# parport.net
KiCad netlist of a schematic drawn in EAGLE
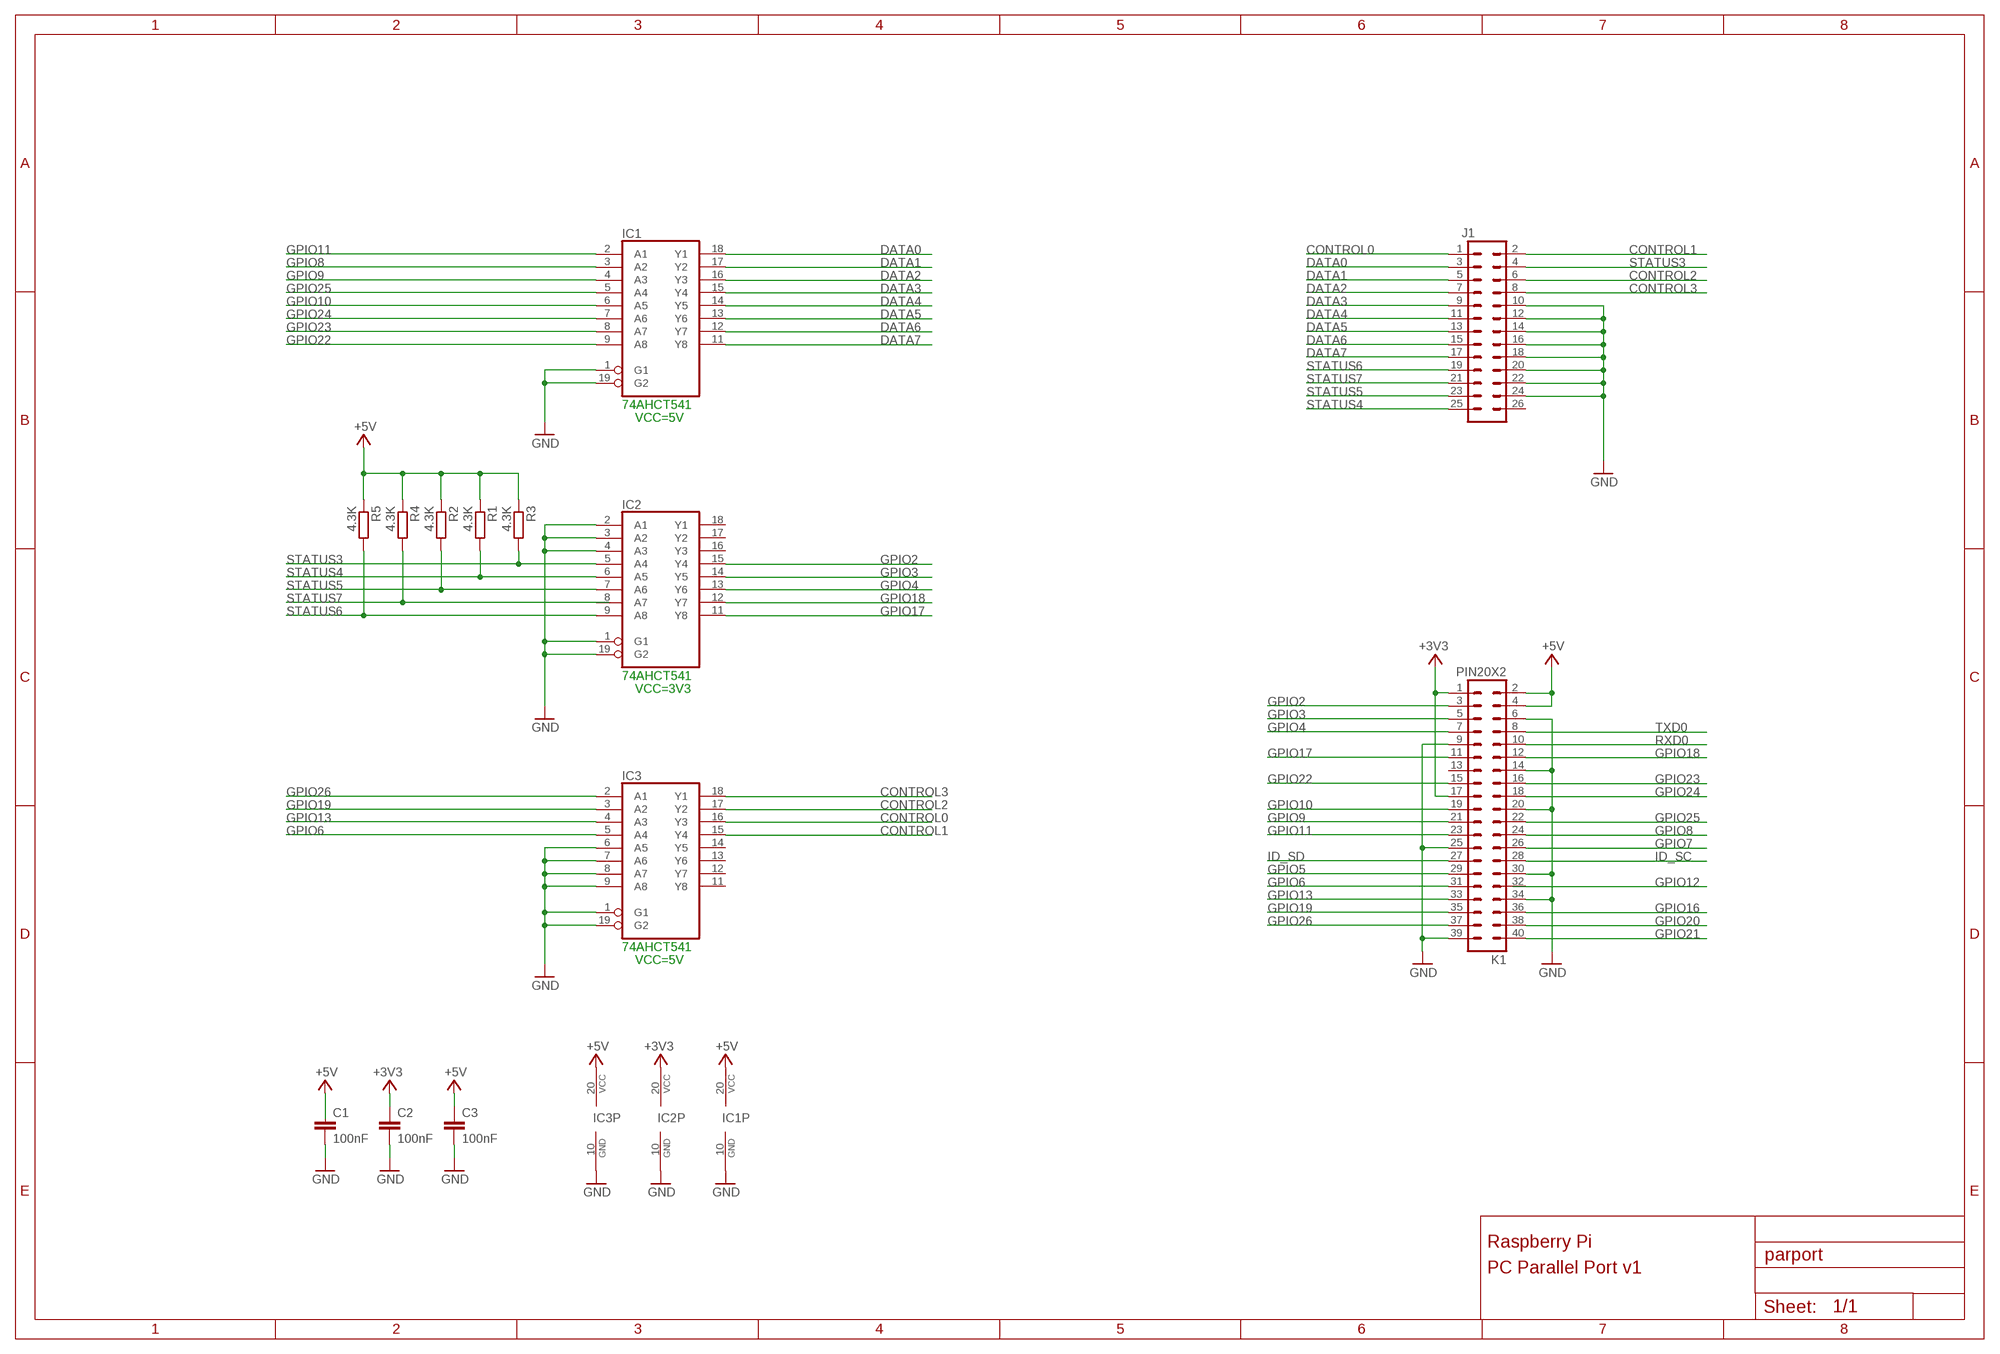
[diagram p0: schematic, sheet 1]

(export (version "E")
  (design (tool "Eeschema 10.0.6"))
  (components
    (comp (ref "C1")
      (value "100nF")
      (footprint "eagle-import:C0805")
      (libsource (lib "eagle-import") (part "C-EUC0805"))
    )
    (comp (ref "C2")
      (value "100nF")
      (footprint "eagle-import:C0805")
      (libsource (lib "eagle-import") (part "C-EUC0805"))
    )
    (comp (ref "C3")
      (value "100nF")
      (footprint "eagle-import:C0805")
      (libsource (lib "eagle-import") (part "C-EUC0805"))
    )
    (comp (ref "IC1")
      (value "74LS541DW")
      (footprint "eagle-import:SO20W")
      (libsource (lib "eagle-import") (part "74541DWLS"))
    )
    (comp (ref "IC2")
      (value "74LS541DW")
      (footprint "eagle-import:SO20W")
      (libsource (lib "eagle-import") (part "74541DWLS"))
    )
    (comp (ref "IC3")
      (value "74LS541DW")
      (footprint "eagle-import:SO20W")
      (libsource (lib "eagle-import") (part "74541DWLS"))
    )
    (comp (ref "J1")
      (value "M13X22X13")
      (footprint "eagle-import:2X13")
      (libsource (lib "eagle-import") (part "M13X22X13"))
    )
    (comp (ref "K1")
      (value "PIN20X2")
      (footprint "eagle-import:PIN_20X2")
      (libsource (lib "eagle-import") (part "PIN20X2"))
    )
    (comp (ref "R1")
      (value "4.3K")
      (footprint "eagle-import:R0805")
      (libsource (lib "eagle-import") (part "R-EU_R0805"))
    )
    (comp (ref "R2")
      (value "4.3K")
      (footprint "eagle-import:R0805")
      (libsource (lib "eagle-import") (part "R-EU_R0805"))
    )
    (comp (ref "R3")
      (value "4.3K")
      (footprint "eagle-import:R0805")
      (libsource (lib "eagle-import") (part "R-EU_R0805"))
    )
    (comp (ref "R4")
      (value "4.3K")
      (footprint "eagle-import:R0805")
      (libsource (lib "eagle-import") (part "R-EU_R0805"))
    )
    (comp (ref "R5")
      (value "4.3K")
      (footprint "eagle-import:R0805")
      (libsource (lib "eagle-import") (part "R-EU_R0805"))
    )
  )
  (nets
    (net (code "1") (name "+3V3") (class "Default")
      (node (ref "C2") (pin "1") (pinfunction "1_1") (pintype "passive"))
      (node (ref "IC2") (pin "20") (pinfunction "VCC_20") (pintype "power_in"))
      (node (ref "K1") (pin "1") (pinfunction "1_1") (pintype "passive"))
      (node (ref "K1") (pin "17") (pinfunction "17_17") (pintype "passive"))
    )
    (net (code "2") (name "+5V") (class "Default")
      (node (ref "C1") (pin "1") (pinfunction "1_1") (pintype "passive"))
      (node (ref "C3") (pin "1") (pinfunction "1_1") (pintype "passive"))
      (node (ref "IC1") (pin "20") (pinfunction "VCC_20") (pintype "power_in"))
      (node (ref "IC3") (pin "20") (pinfunction "VCC_20") (pintype "power_in"))
      (node (ref "K1") (pin "2") (pinfunction "2_2") (pintype "passive"))
      (node (ref "K1") (pin "4") (pinfunction "4_4") (pintype "passive"))
      (node (ref "R1") (pin "1") (pinfunction "1_1") (pintype "passive"))
      (node (ref "R2") (pin "1") (pinfunction "1_1") (pintype "passive"))
      (node (ref "R3") (pin "1") (pinfunction "1_1") (pintype "passive"))
      (node (ref "R4") (pin "1") (pinfunction "1_1") (pintype "passive"))
      (node (ref "R5") (pin "1") (pinfunction "1_1") (pintype "passive"))
    )
    (net (code "3") (name "/CONTROL0") (class "Default")
      (node (ref "IC3") (pin "16") (pinfunction "Y3_16") (pintype "tri_state"))
      (node (ref "J1") (pin "1") (pinfunction "1_1") (pintype "passive"))
    )
    (net (code "4") (name "/CONTROL1") (class "Default")
      (node (ref "IC3") (pin "15") (pinfunction "Y4_15") (pintype "tri_state"))
      (node (ref "J1") (pin "2") (pinfunction "2_2") (pintype "passive"))
    )
    (net (code "5") (name "/CONTROL2") (class "Default")
      (node (ref "IC3") (pin "17") (pinfunction "Y2_17") (pintype "tri_state"))
      (node (ref "J1") (pin "6") (pinfunction "6_6") (pintype "passive"))
    )
    (net (code "6") (name "/CONTROL3") (class "Default")
      (node (ref "IC3") (pin "18") (pinfunction "Y1_18") (pintype "tri_state"))
      (node (ref "J1") (pin "8") (pinfunction "8_8") (pintype "passive"))
    )
    (net (code "7") (name "/DATA0") (class "Default")
      (node (ref "IC1") (pin "18") (pinfunction "Y1_18") (pintype "tri_state"))
      (node (ref "J1") (pin "3") (pinfunction "3_3") (pintype "passive"))
    )
    (net (code "8") (name "/DATA1") (class "Default")
      (node (ref "IC1") (pin "17") (pinfunction "Y2_17") (pintype "tri_state"))
      (node (ref "J1") (pin "5") (pinfunction "5_5") (pintype "passive"))
    )
    (net (code "9") (name "/DATA2") (class "Default")
      (node (ref "IC1") (pin "16") (pinfunction "Y3_16") (pintype "tri_state"))
      (node (ref "J1") (pin "7") (pinfunction "7_7") (pintype "passive"))
    )
    (net (code "10") (name "/DATA3") (class "Default")
      (node (ref "IC1") (pin "15") (pinfunction "Y4_15") (pintype "tri_state"))
      (node (ref "J1") (pin "9") (pinfunction "9_9") (pintype "passive"))
    )
    (net (code "11") (name "/DATA4") (class "Default")
      (node (ref "IC1") (pin "14") (pinfunction "Y5_14") (pintype "tri_state"))
      (node (ref "J1") (pin "11") (pinfunction "11_11") (pintype "passive"))
    )
    (net (code "12") (name "/DATA5") (class "Default")
      (node (ref "IC1") (pin "13") (pinfunction "Y6_13") (pintype "tri_state"))
      (node (ref "J1") (pin "13") (pinfunction "13_13") (pintype "passive"))
    )
    (net (code "13") (name "/DATA6") (class "Default")
      (node (ref "IC1") (pin "12") (pinfunction "Y7_12") (pintype "tri_state"))
      (node (ref "J1") (pin "15") (pinfunction "15_15") (pintype "passive"))
    )
    (net (code "14") (name "/DATA7") (class "Default")
      (node (ref "IC1") (pin "11") (pinfunction "Y8_11") (pintype "tri_state"))
      (node (ref "J1") (pin "17") (pinfunction "17_17") (pintype "passive"))
    )
    (net (code "15") (name "/GPIO2") (class "Default")
      (node (ref "IC2") (pin "15") (pinfunction "Y4_15") (pintype "tri_state"))
      (node (ref "K1") (pin "3") (pinfunction "3_3") (pintype "passive"))
    )
    (net (code "16") (name "/GPIO3") (class "Default")
      (node (ref "IC2") (pin "14") (pinfunction "Y5_14") (pintype "tri_state"))
      (node (ref "K1") (pin "5") (pinfunction "5_5") (pintype "passive"))
    )
    (net (code "17") (name "/GPIO4") (class "Default")
      (node (ref "IC2") (pin "13") (pinfunction "Y6_13") (pintype "tri_state"))
      (node (ref "K1") (pin "7") (pinfunction "7_7") (pintype "passive"))
    )
    (net (code "18") (name "/GPIO5") (class "Default")
      (node (ref "K1") (pin "29") (pinfunction "29_29") (pintype "passive"))
    )
    (net (code "19") (name "/GPIO6") (class "Default")
      (node (ref "IC3") (pin "5") (pinfunction "A4_5") (pintype "input"))
      (node (ref "K1") (pin "31") (pinfunction "31_31") (pintype "passive"))
    )
    (net (code "20") (name "/GPIO7") (class "Default")
      (node (ref "K1") (pin "26") (pinfunction "26_26") (pintype "passive"))
    )
    (net (code "21") (name "/GPIO8") (class "Default")
      (node (ref "IC1") (pin "3") (pinfunction "A2_3") (pintype "input"))
      (node (ref "K1") (pin "24") (pinfunction "24_24") (pintype "passive"))
    )
    (net (code "22") (name "/GPIO9") (class "Default")
      (node (ref "IC1") (pin "4") (pinfunction "A3_4") (pintype "input"))
      (node (ref "K1") (pin "21") (pinfunction "21_21") (pintype "passive"))
    )
    (net (code "23") (name "/GPIO10") (class "Default")
      (node (ref "IC1") (pin "6") (pinfunction "A5_6") (pintype "input"))
      (node (ref "K1") (pin "19") (pinfunction "19_19") (pintype "passive"))
    )
    (net (code "24") (name "/GPIO11") (class "Default")
      (node (ref "IC1") (pin "2") (pinfunction "A1_2") (pintype "input"))
      (node (ref "K1") (pin "23") (pinfunction "23_23") (pintype "passive"))
    )
    (net (code "26") (name "/GPIO13") (class "Default")
      (node (ref "IC3") (pin "4") (pinfunction "A3_4") (pintype "input"))
      (node (ref "K1") (pin "33") (pinfunction "33_33") (pintype "passive"))
    )
    (net (code "27") (name "/GPIO16") (class "Default")
      (node (ref "K1") (pin "36") (pinfunction "36_36") (pintype "passive"))
    )
    (net (code "28") (name "/GPIO17") (class "Default")
      (node (ref "IC2") (pin "11") (pinfunction "Y8_11") (pintype "tri_state"))
      (node (ref "K1") (pin "11") (pinfunction "11_11") (pintype "passive"))
    )
    (net (code "29") (name "/GPIO18") (class "Default")
      (node (ref "IC2") (pin "12") (pinfunction "Y7_12") (pintype "tri_state"))
      (node (ref "K1") (pin "12") (pinfunction "12_12") (pintype "passive"))
    )
    (net (code "30") (name "/GPIO19") (class "Default")
      (node (ref "IC3") (pin "3") (pinfunction "A2_3") (pintype "input"))
      (node (ref "K1") (pin "35") (pinfunction "35_35") (pintype "passive"))
    )
    (net (code "31") (name "/GPIO20") (class "Default")
      (node (ref "K1") (pin "38") (pinfunction "38_38") (pintype "passive"))
    )
    (net (code "32") (name "/GPIO21") (class "Default")
      (node (ref "K1") (pin "40") (pinfunction "40_40") (pintype "passive"))
    )
    (net (code "33") (name "/GPIO22") (class "Default")
      (node (ref "IC1") (pin "9") (pinfunction "A8_9") (pintype "input"))
      (node (ref "K1") (pin "15") (pinfunction "15_15") (pintype "passive"))
    )
    (net (code "34") (name "/GPIO23") (class "Default")
      (node (ref "IC1") (pin "8") (pinfunction "A7_8") (pintype "input"))
      (node (ref "K1") (pin "16") (pinfunction "16_16") (pintype "passive"))
    )
    (net (code "35") (name "/GPIO24") (class "Default")
      (node (ref "IC1") (pin "7") (pinfunction "A6_7") (pintype "input"))
      (node (ref "K1") (pin "18") (pinfunction "18_18") (pintype "passive"))
    )
    (net (code "36") (name "/GPIO25") (class "Default")
      (node (ref "IC1") (pin "5") (pinfunction "A4_5") (pintype "input"))
      (node (ref "K1") (pin "22") (pinfunction "22_22") (pintype "passive"))
    )
    (net (code "37") (name "/GPIO26") (class "Default")
      (node (ref "IC3") (pin "2") (pinfunction "A1_2") (pintype "input"))
      (node (ref "K1") (pin "37") (pinfunction "37_37") (pintype "passive"))
    )
    (net (code "38") (name "/ID_SC") (class "Default")
      (node (ref "K1") (pin "28") (pinfunction "28_28") (pintype "passive"))
    )
    (net (code "39") (name "/ID_SD") (class "Default")
      (node (ref "K1") (pin "27") (pinfunction "27_27") (pintype "passive"))
    )
    (net (code "40") (name "/RXD0") (class "Default")
      (node (ref "K1") (pin "10") (pinfunction "10_10") (pintype "passive"))
    )
    (net (code "41") (name "/STATUS3") (class "Default")
      (node (ref "IC2") (pin "5") (pinfunction "A4_5") (pintype "input"))
      (node (ref "J1") (pin "4") (pinfunction "4_4") (pintype "passive"))
      (node (ref "R3") (pin "2") (pinfunction "2_2") (pintype "passive"))
    )
    (net (code "42") (name "/STATUS4") (class "Default")
      (node (ref "IC2") (pin "6") (pinfunction "A5_6") (pintype "input"))
      (node (ref "J1") (pin "25") (pinfunction "25_25") (pintype "passive"))
      (node (ref "R1") (pin "2") (pinfunction "2_2") (pintype "passive"))
    )
    (net (code "43") (name "/STATUS5") (class "Default")
      (node (ref "IC2") (pin "7") (pinfunction "A6_7") (pintype "input"))
      (node (ref "J1") (pin "23") (pinfunction "23_23") (pintype "passive"))
      (node (ref "R2") (pin "2") (pinfunction "2_2") (pintype "passive"))
    )
    (net (code "44") (name "/STATUS6") (class "Default")
      (node (ref "IC2") (pin "9") (pinfunction "A8_9") (pintype "input"))
      (node (ref "J1") (pin "19") (pinfunction "19_19") (pintype "passive"))
      (node (ref "R5") (pin "2") (pinfunction "2_2") (pintype "passive"))
    )
    (net (code "45") (name "/STATUS7") (class "Default")
      (node (ref "IC2") (pin "8") (pinfunction "A7_8") (pintype "input"))
      (node (ref "J1") (pin "21") (pinfunction "21_21") (pintype "passive"))
      (node (ref "R4") (pin "2") (pinfunction "2_2") (pintype "passive"))
    )
    (net (code "46") (name "/TXD0") (class "Default")
      (node (ref "K1") (pin "8") (pinfunction "8_8") (pintype "passive"))
    )
    (net (code "47") (name "GND") (class "Default")
      (node (ref "C1") (pin "2") (pinfunction "2_2") (pintype "passive"))
      (node (ref "C2") (pin "2") (pinfunction "2_2") (pintype "passive"))
      (node (ref "C3") (pin "2") (pinfunction "2_2") (pintype "passive"))
      (node (ref "IC1") (pin "1") (pinfunction "G1_1") (pintype "input"))
      (node (ref "IC1") (pin "10") (pinfunction "GND_10") (pintype "power_in"))
      (node (ref "IC1") (pin "19") (pinfunction "G2_19") (pintype "input"))
      (node (ref "IC2") (pin "1") (pinfunction "G1_1") (pintype "input"))
      (node (ref "IC2") (pin "10") (pinfunction "GND_10") (pintype "power_in"))
      (node (ref "IC2") (pin "19") (pinfunction "G2_19") (pintype "input"))
      (node (ref "IC2") (pin "2") (pinfunction "A1_2") (pintype "input"))
      (node (ref "IC2") (pin "3") (pinfunction "A2_3") (pintype "input"))
      (node (ref "IC2") (pin "4") (pinfunction "A3_4") (pintype "input"))
      (node (ref "IC3") (pin "1") (pinfunction "G1_1") (pintype "input"))
      (node (ref "IC3") (pin "10") (pinfunction "GND_10") (pintype "power_in"))
      (node (ref "IC3") (pin "19") (pinfunction "G2_19") (pintype "input"))
      (node (ref "IC3") (pin "6") (pinfunction "A5_6") (pintype "input"))
      (node (ref "IC3") (pin "7") (pinfunction "A6_7") (pintype "input"))
      (node (ref "IC3") (pin "8") (pinfunction "A7_8") (pintype "input"))
      (node (ref "IC3") (pin "9") (pinfunction "A8_9") (pintype "input"))
      (node (ref "J1") (pin "10") (pinfunction "10_10") (pintype "passive"))
      (node (ref "J1") (pin "12") (pinfunction "12_12") (pintype "passive"))
      (node (ref "J1") (pin "14") (pinfunction "14_14") (pintype "passive"))
      (node (ref "J1") (pin "16") (pinfunction "16_16") (pintype "passive"))
      (node (ref "J1") (pin "18") (pinfunction "18_18") (pintype "passive"))
      (node (ref "J1") (pin "20") (pinfunction "20_20") (pintype "passive"))
      (node (ref "J1") (pin "22") (pinfunction "22_22") (pintype "passive"))
      (node (ref "J1") (pin "24") (pinfunction "24_24") (pintype "passive"))
      (node (ref "K1") (pin "14") (pinfunction "14_14") (pintype "passive"))
      (node (ref "K1") (pin "20") (pinfunction "20_20") (pintype "passive"))
      (node (ref "K1") (pin "25") (pinfunction "25_25") (pintype "passive"))
      (node (ref "K1") (pin "30") (pinfunction "30_30") (pintype "passive"))
      (node (ref "K1") (pin "34") (pinfunction "34_34") (pintype "passive"))
      (node (ref "K1") (pin "39") (pinfunction "39_39") (pintype "passive"))
      (node (ref "K1") (pin "6") (pinfunction "6_6") (pintype "passive"))
      (node (ref "K1") (pin "9") (pinfunction "9_9") (pintype "passive"))
    )
    (net (code "48") (name "unconnected-(IC2A-Y1-Pad18)") (class "Default")
      (node (ref "IC2") (pin "18") (pinfunction "Y1_18") (pintype "tri_state"))
    )
    (net (code "49") (name "unconnected-(IC2A-Y2-Pad17)") (class "Default")
      (node (ref "IC2") (pin "17") (pinfunction "Y2_17") (pintype "tri_state"))
    )
    (net (code "50") (name "unconnected-(IC2A-Y3-Pad16)") (class "Default")
      (node (ref "IC2") (pin "16") (pinfunction "Y3_16") (pintype "tri_state"))
    )
    (net (code "51") (name "unconnected-(IC3A-Y5-Pad14)") (class "Default")
      (node (ref "IC3") (pin "14") (pinfunction "Y5_14") (pintype "tri_state"))
    )
    (net (code "52") (name "unconnected-(IC3A-Y6-Pad13)") (class "Default")
      (node (ref "IC3") (pin "13") (pinfunction "Y6_13") (pintype "tri_state"))
    )
    (net (code "53") (name "unconnected-(IC3A-Y7-Pad12)") (class "Default")
      (node (ref "IC3") (pin "12") (pinfunction "Y7_12") (pintype "tri_state"))
    )
    (net (code "54") (name "unconnected-(IC3A-Y8-Pad11)") (class "Default")
      (node (ref "IC3") (pin "11") (pinfunction "Y8_11") (pintype "tri_state"))
    )
    (net (code "55") (name "unconnected-(J1-Pad26)") (class "Default")
      (node (ref "J1") (pin "26") (pinfunction "26_26") (pintype "passive"))
    )
    (net (code "56") (name "unconnected-(K1-Pad13)") (class "Default")
      (node (ref "K1") (pin "13") (pinfunction "13_13") (pintype "passive"))
    )
    (net (code "57") (name "unconnected-(K1-Pad32)") (class "Default")
      (node (ref "K1") (pin "32") (pinfunction "32_32") (pintype "passive"))
    )
  )
)
